# Serial.net
KiCad netlist of a schematic drawn in EAGLE
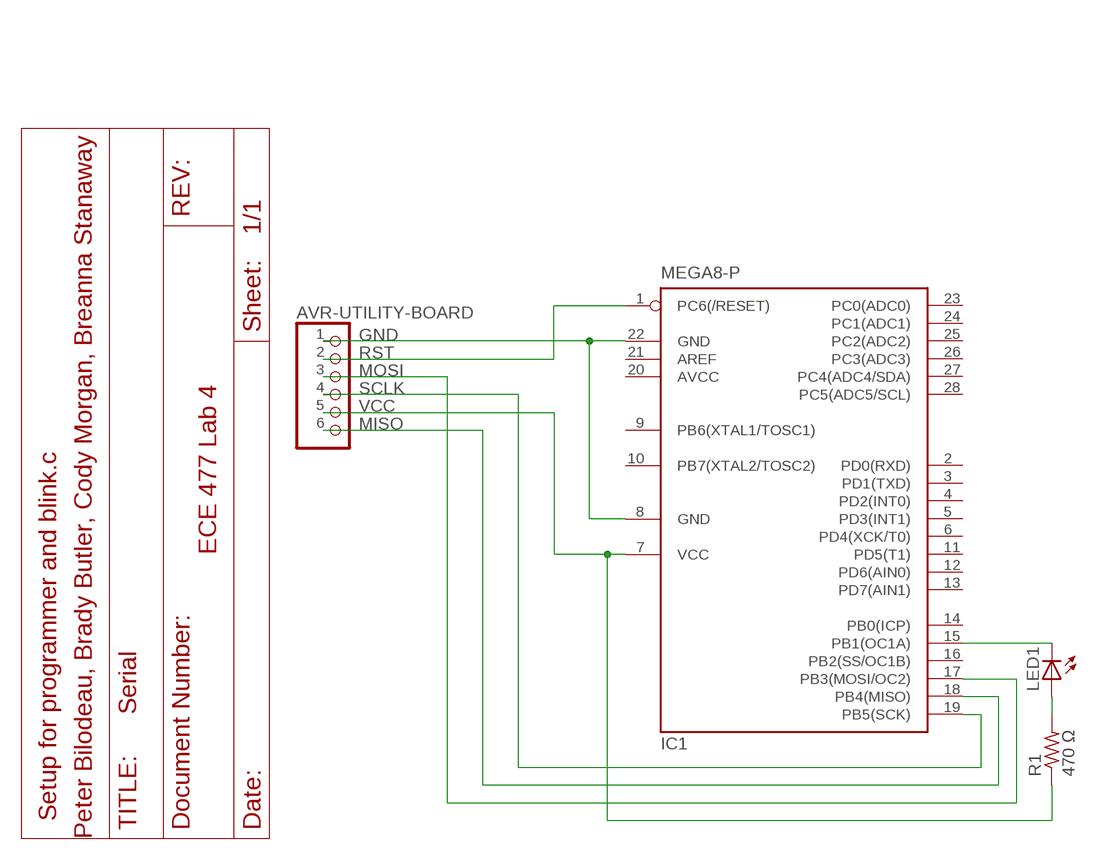
[diagram p0: schematic, sheet 1]

(export (version "E")
  (design (tool "Eeschema 10.0.6"))
  (components
    (comp (ref "AVR-UTILITY-BOARD")
      (value "PINHD-1X6")
      (footprint "eagle-import:1X06")
      (libsource (lib "eagle-import") (part "PINHD-1X6"))
    )
    (comp (ref "IC1")
      (value "MEGA8-P")
      (footprint "eagle-import:DIL28-3")
      (libsource (lib "eagle-import") (part "MEGA8-P"))
    )
    (comp (ref "LED1")
      (value "LED3MM")
      (footprint "eagle-import:LED3MM")
      (libsource (lib "eagle-import") (part "LED3MM"))
    )
    (comp (ref "R1")
      (value "470 Ω")
      (footprint "eagle-import:0204V")
      (libsource (lib "eagle-import") (part "R-US_0204/2V"))
    )
  )
  (nets
    (net (code "1") (name "/AVCC") (class "Default")
      (node (ref "IC1") (pin "20") (pinfunction "AVCC_20") (pintype "power_in"))
    )
    (net (code "2") (name "/GND") (class "Default")
      (node (ref "AVR-UTILITY-BOARD") (pin "1") (pinfunction "1_1") (pintype "passive"))
      (node (ref "IC1") (pin "22") (pinfunction "GND_22") (pintype "power_in"))
      (node (ref "IC1") (pin "8") (pinfunction "GND_8") (pintype "power_in"))
    )
    (net (code "3") (name "/MISO") (class "Default")
      (node (ref "AVR-UTILITY-BOARD") (pin "6") (pinfunction "6_6") (pintype "passive"))
      (node (ref "IC1") (pin "18") (pinfunction "PB4(MISO)_18") (pintype "bidirectional"))
    )
    (net (code "4") (name "/MOSI") (class "Default")
      (node (ref "AVR-UTILITY-BOARD") (pin "3") (pinfunction "3_3") (pintype "passive"))
      (node (ref "IC1") (pin "17") (pinfunction "PB3(MOSI/OC2)_17") (pintype "bidirectional"))
    )
    (net (code "5") (name "/RST") (class "Default")
      (node (ref "AVR-UTILITY-BOARD") (pin "2") (pinfunction "2_2") (pintype "passive"))
      (node (ref "IC1") (pin "1") (pinfunction "PC6(/RESET)_1") (pintype "bidirectional"))
    )
    (net (code "6") (name "/SCLK") (class "Default")
      (node (ref "AVR-UTILITY-BOARD") (pin "4") (pinfunction "4_4") (pintype "passive"))
      (node (ref "IC1") (pin "19") (pinfunction "PB5(SCK)_19") (pintype "bidirectional"))
    )
    (net (code "7") (name "/VCC") (class "Default")
      (node (ref "AVR-UTILITY-BOARD") (pin "5") (pinfunction "5_5") (pintype "passive"))
      (node (ref "IC1") (pin "7") (pinfunction "VCC_7") (pintype "power_in"))
      (node (ref "R1") (pin "1") (pinfunction "1_1") (pintype "passive"))
    )
    (net (code "8") (name "Net-(IC1-PB1(OC1A))") (class "Default")
      (node (ref "IC1") (pin "15") (pinfunction "PB1(OC1A)_15") (pintype "bidirectional"))
      (node (ref "LED1") (pin "K") (pinfunction "C_K") (pintype "passive"))
    )
    (net (code "9") (name "Net-(LED1-PadA)") (class "Default")
      (node (ref "LED1") (pin "A") (pinfunction "A_A") (pintype "passive"))
      (node (ref "R1") (pin "2") (pinfunction "2_2") (pintype "passive"))
    )
    (net (code "10") (name "unconnected-(IC1-AREF-Pad21)") (class "Default")
      (node (ref "IC1") (pin "21") (pinfunction "AREF_21") (pintype "passive"))
    )
    (net (code "11") (name "unconnected-(IC1-PB0(ICP)-Pad14)") (class "Default")
      (node (ref "IC1") (pin "14") (pinfunction "PB0(ICP)_14") (pintype "bidirectional"))
    )
    (net (code "12") (name "unconnected-(IC1-PB2(SS{slash}OC1B)-Pad16)") (class "Default")
      (node (ref "IC1") (pin "16") (pinfunction "PB2(SS/OC1B)_16") (pintype "bidirectional"))
    )
    (net (code "13") (name "unconnected-(IC1-PB6(XTAL1{slash}TOSC1)-Pad9)") (class "Default")
      (node (ref "IC1") (pin "9") (pinfunction "PB6(XTAL1/TOSC1)_9") (pintype "bidirectional"))
    )
    (net (code "14") (name "unconnected-(IC1-PB7(XTAL2{slash}TOSC2)-Pad10)") (class "Default")
      (node (ref "IC1") (pin "10") (pinfunction "PB7(XTAL2/TOSC2)_10") (pintype "bidirectional"))
    )
    (net (code "15") (name "unconnected-(IC1-PC0(ADC0)-Pad23)") (class "Default")
      (node (ref "IC1") (pin "23") (pinfunction "PC0(ADC0)_23") (pintype "bidirectional"))
    )
    (net (code "16") (name "unconnected-(IC1-PC1(ADC1)-Pad24)") (class "Default")
      (node (ref "IC1") (pin "24") (pinfunction "PC1(ADC1)_24") (pintype "bidirectional"))
    )
    (net (code "17") (name "unconnected-(IC1-PC2(ADC2)-Pad25)") (class "Default")
      (node (ref "IC1") (pin "25") (pinfunction "PC2(ADC2)_25") (pintype "bidirectional"))
    )
    (net (code "18") (name "unconnected-(IC1-PC3(ADC3)-Pad26)") (class "Default")
      (node (ref "IC1") (pin "26") (pinfunction "PC3(ADC3)_26") (pintype "bidirectional"))
    )
    (net (code "19") (name "unconnected-(IC1-PC4(ADC4{slash}SDA)-Pad27)") (class "Default")
      (node (ref "IC1") (pin "27") (pinfunction "PC4(ADC4/SDA)_27") (pintype "bidirectional"))
    )
    (net (code "20") (name "unconnected-(IC1-PC5(ADC5{slash}SCL)-Pad28)") (class "Default")
      (node (ref "IC1") (pin "28") (pinfunction "PC5(ADC5/SCL)_28") (pintype "bidirectional"))
    )
    (net (code "21") (name "unconnected-(IC1-PD0(RXD)-Pad2)") (class "Default")
      (node (ref "IC1") (pin "2") (pinfunction "PD0(RXD)_2") (pintype "bidirectional"))
    )
    (net (code "22") (name "unconnected-(IC1-PD1(TXD)-Pad3)") (class "Default")
      (node (ref "IC1") (pin "3") (pinfunction "PD1(TXD)_3") (pintype "bidirectional"))
    )
    (net (code "23") (name "unconnected-(IC1-PD2(INT0)-Pad4)") (class "Default")
      (node (ref "IC1") (pin "4") (pinfunction "PD2(INT0)_4") (pintype "bidirectional"))
    )
    (net (code "24") (name "unconnected-(IC1-PD3(INT1)-Pad5)") (class "Default")
      (node (ref "IC1") (pin "5") (pinfunction "PD3(INT1)_5") (pintype "bidirectional"))
    )
    (net (code "25") (name "unconnected-(IC1-PD4(XCK{slash}T0)-Pad6)") (class "Default")
      (node (ref "IC1") (pin "6") (pinfunction "PD4(XCK/T0)_6") (pintype "bidirectional"))
    )
    (net (code "26") (name "unconnected-(IC1-PD5(T1)-Pad11)") (class "Default")
      (node (ref "IC1") (pin "11") (pinfunction "PD5(T1)_11") (pintype "bidirectional"))
    )
    (net (code "27") (name "unconnected-(IC1-PD6(AIN0)-Pad12)") (class "Default")
      (node (ref "IC1") (pin "12") (pinfunction "PD6(AIN0)_12") (pintype "bidirectional"))
    )
    (net (code "28") (name "unconnected-(IC1-PD7(AIN1)-Pad13)") (class "Default")
      (node (ref "IC1") (pin "13") (pinfunction "PD7(AIN1)_13") (pintype "bidirectional"))
    )
  )
)
